# bikealarmf.net
KiCad netlist of a schematic drawn in EAGLE
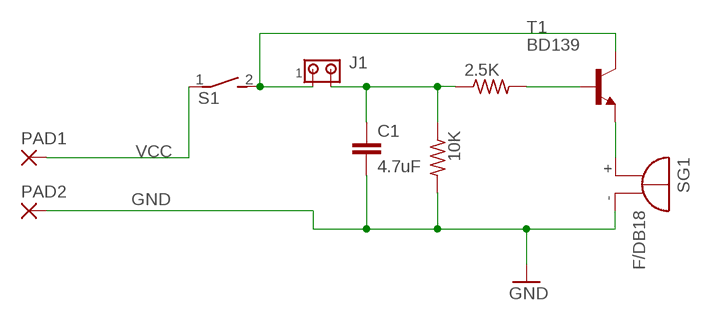
[diagram p0: schematic, sheet 1]

(export (version "E")
  (design (tool "Eeschema 10.0.6"))
  (components
    (comp (ref "2.5K")
      (value "R-US_0204/7")
      (footprint "eagle-import:0204_7")
      (libsource (lib "eagle-import") (part "R-US_0204/7"))
    )
    (comp (ref "10K")
      (value "R-US_0204/7")
      (footprint "eagle-import:0204_7")
      (libsource (lib "eagle-import") (part "R-US_0204/7"))
    )
    (comp (ref "C1")
      (value "4.7uF")
      (footprint "eagle-import:C025-030X050")
      (libsource (lib "eagle-import") (part "C-EU025-030X050"))
    )
    (comp (ref "J1")
      (value "MTA02-156")
      (footprint "eagle-import:1X2MTA")
      (libsource (lib "eagle-import") (part "MTA02-156"))
    )
    (comp (ref "PAD1")
      (value "2,15/1,0")
      (footprint "eagle-import:2,15_1,0")
      (libsource (lib "eagle-import") (part "2,15/1,0"))
    )
    (comp (ref "PAD2")
      (value "2,15/1,0")
      (footprint "eagle-import:2,15_1,0")
      (libsource (lib "eagle-import") (part "2,15/1,0"))
    )
    (comp (ref "S1")
      (value "DS01E")
      (footprint "eagle-import:DS-01")
      (libsource (lib "eagle-import") (part "DS01E"))
    )
    (comp (ref "SG1")
      (value "F/DB18")
      (footprint "eagle-import:F_DB18")
      (libsource (lib "eagle-import") (part "F/DB18"))
    )
    (comp (ref "T1")
      (value "BD139")
      (footprint "eagle-import:TO126")
      (libsource (lib "eagle-import") (part "BD139"))
    )
  )
  (nets
    (net (code "1") (name "/VCC") (class "Default")
      (node (ref "PAD1") (pin "1") (pinfunction "P_1") (pintype "passive"))
      (node (ref "S1") (pin "1") (pinfunction "1_1") (pintype "passive"))
    )
    (net (code "2") (name "GND") (class "Default")
      (node (ref "10K") (pin "2") (pinfunction "2_2") (pintype "passive"))
      (node (ref "C1") (pin "2") (pinfunction "2_2") (pintype "passive"))
      (node (ref "J1") (pin "1") (pinfunction "1_1") (pintype "passive"))
      (node (ref "PAD2") (pin "1") (pinfunction "P_1") (pintype "passive"))
      (node (ref "S1") (pin "2") (pinfunction "2_2") (pintype "passive"))
      (node (ref "SG1") (pin "-") (pinfunction "-_-") (pintype "passive"))
      (node (ref "T1") (pin "2") (pinfunction "C_2") (pintype "passive"))
    )
    (net (code "3") (name "Net-(10K-Pad1)") (class "Default")
      (node (ref "10K") (pin "1") (pinfunction "1_1") (pintype "passive"))
      (node (ref "2.5K") (pin "1") (pinfunction "1_1") (pintype "passive"))
      (node (ref "C1") (pin "1") (pinfunction "1_1") (pintype "passive"))
      (node (ref "J1") (pin "2") (pinfunction "2_2") (pintype "passive"))
    )
    (net (code "4") (name "Net-(T1-B)") (class "Default")
      (node (ref "2.5K") (pin "2") (pinfunction "2_2") (pintype "passive"))
      (node (ref "T1") (pin "3") (pinfunction "B_3") (pintype "passive"))
    )
    (net (code "5") (name "Net-(T1-E)") (class "Default")
      (node (ref "SG1") (pin "+") (pinfunction "+_+") (pintype "passive"))
      (node (ref "T1") (pin "1") (pinfunction "E_1") (pintype "passive"))
    )
  )
)
